# ReadyUNO_DIP.net
KiCad netlist of a schematic drawn in EAGLE
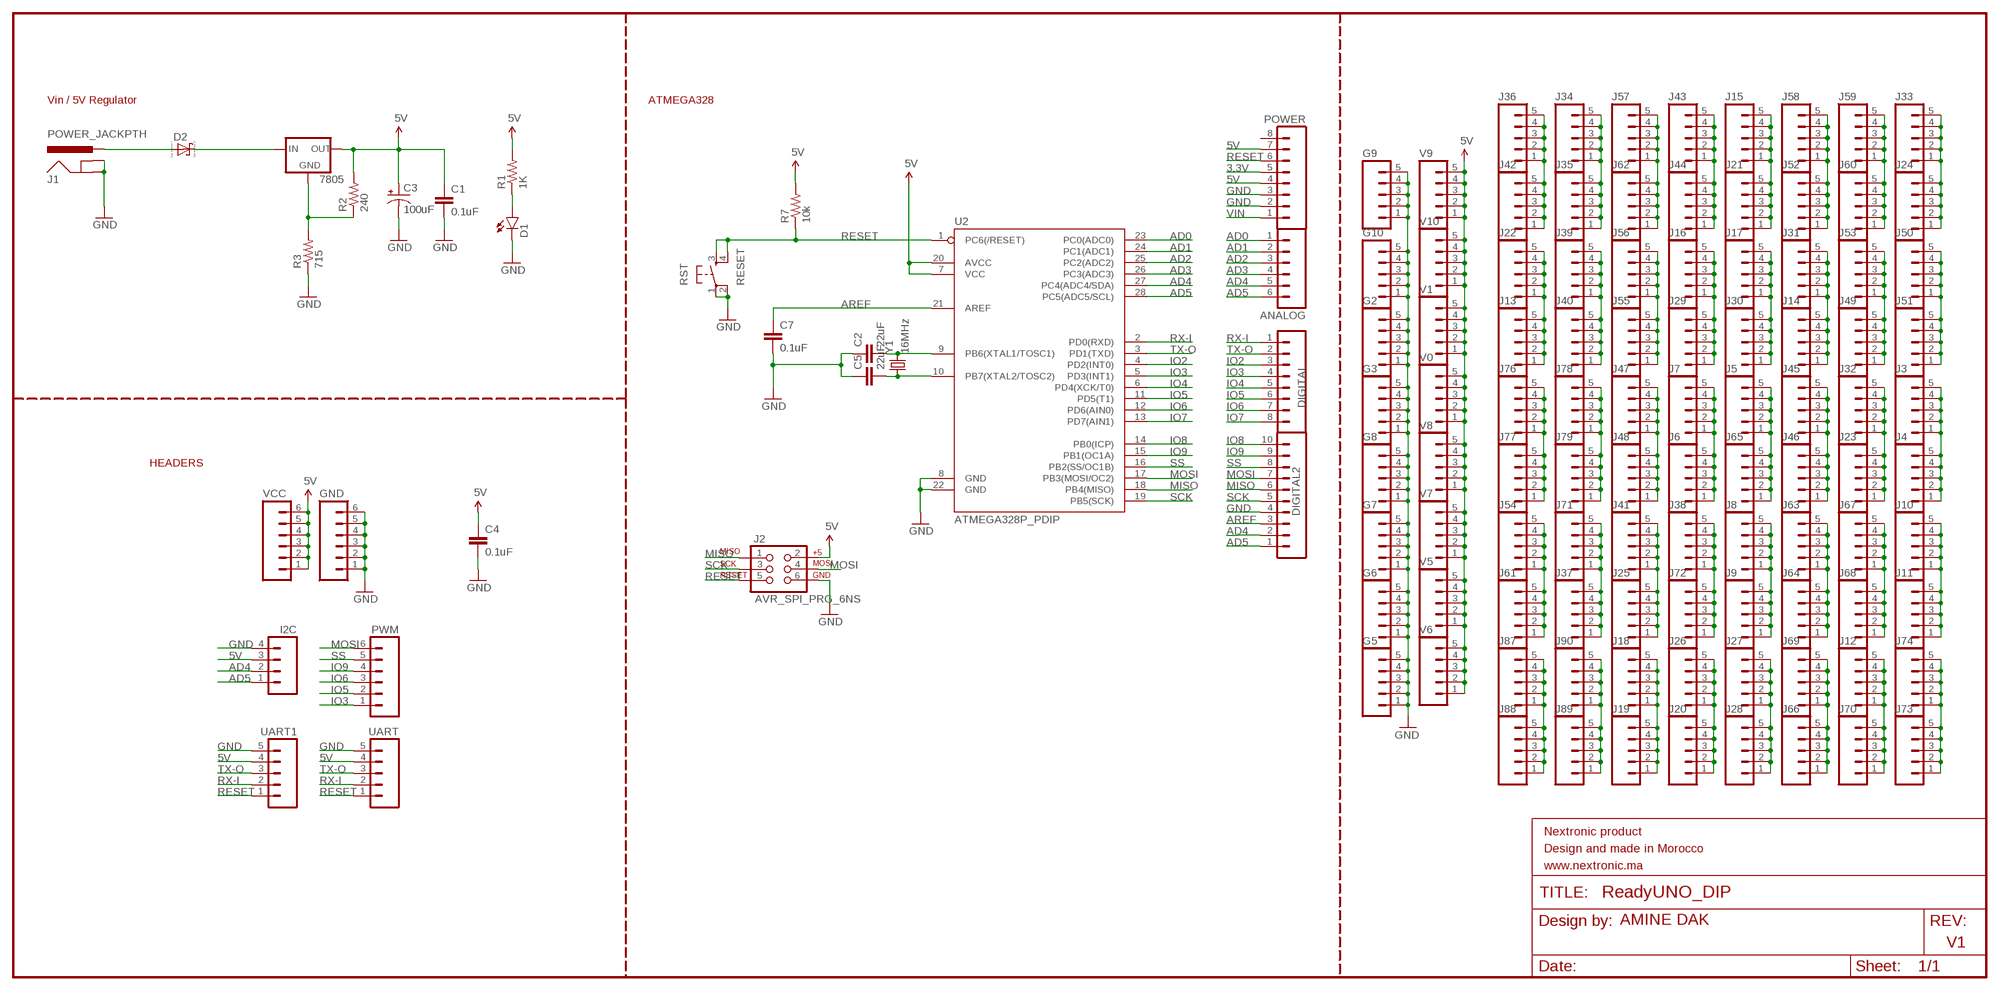
[diagram p0: schematic, sheet 1]

(export (version "E")
  (design (tool "Eeschema 10.0.6"))
  (components
    (comp (ref "7805")
      (value "V_REG_78XX-TO-220")
      (footprint "eagle-import:TO-220-ALT")
      (libsource (lib "eagle-import") (part "V_REG_78XX-TO-220"))
    )
    (comp (ref "ANALOG")
      (value "M06SILK_FEMALE_PTH")
      (footprint "eagle-import:1X06")
      (libsource (lib "eagle-import") (part "M06SILK_FEMALE_PTH"))
    )
    (comp (ref "C1")
      (value "0.1uF")
      (footprint "eagle-import:CAP-PTH-SMALLEZ")
      (fields (field (name "MF") "MULTICOMP") (field (name "MPN") "MCRR25104X7RK0050"))
      (libsource (lib "eagle-import") (part "CAPEZ"))
    )
    (comp (ref "C2")
      (value "22uF")
      (footprint "eagle-import:CAP-PTH-SMALLEZ")
      (fields (field (name "MF") "MULTICOMP") (field (name "MPN") "MCGPR100V226M8X11"))
      (libsource (lib "eagle-import") (part "CAPEZ"))
    )
    (comp (ref "C3")
      (value "100uF")
      (footprint "eagle-import:CPOL-RADIAL-100UF-25V")
      (fields (field (name "MF") "MULTICOMP") (field (name "MPN") "MCGPR25V107M6.3X11"))
      (libsource (lib "eagle-import") (part "CAP_POLPTH1"))
    )
    (comp (ref "C4")
      (value "0.1uF")
      (footprint "eagle-import:CAP-PTH-SMALLEZ")
      (fields (field (name "MF") "MULTICOMP") (field (name "MPN") "MCRR25104X7RK0050"))
      (libsource (lib "eagle-import") (part "CAPEZ"))
    )
    (comp (ref "C5")
      (value "22uF")
      (footprint "eagle-import:CAP-PTH-SMALLEZ")
      (fields (field (name "MF") "MULTICOMP") (field (name "MPN") "MCGPR100V226M8X11"))
      (libsource (lib "eagle-import") (part "CAPEZ"))
    )
    (comp (ref "C7")
      (value "0.1uF")
      (footprint "eagle-import:CAP-PTH-SMALLEZ")
      (fields (field (name "MF") "MULTICOMP") (field (name "MPN") "MCRR25104X7RK0050"))
      (libsource (lib "eagle-import") (part "CAPEZ"))
    )
    (comp (ref "D1")
      (value "LED-3MM-NO_SILK")
      (footprint "eagle-import:LED3MM-NS")
      (libsource (lib "eagle-import") (part "LED-3MM-NO_SILK"))
    )
    (comp (ref "D2")
      (value "SCHOTTKY-DIODEDO35-7")
      (footprint "eagle-import:DIODE_DO35-7")
      (libsource (lib "eagle-import") (part "SCHOTTKY-DIODEDO35-7"))
    )
    (comp (ref "DIGITAL")
      (value "M08SILK_FEMALE_PTH")
      (footprint "eagle-import:1X08")
      (libsource (lib "eagle-import") (part "M08SILK_FEMALE_PTH"))
    )
    (comp (ref "DIGITAL2")
      (value "M10SILK_FEMALE_PTH")
      (footprint "eagle-import:1X10")
      (libsource (lib "eagle-import") (part "M10SILK_FEMALE_PTH"))
    )
    (comp (ref "FRAME1")
      (value "FRAME-LETTER")
      (footprint "eagle-import:CREATIVE_COMMONS")
      (libsource (lib "eagle-import") (part "FRAME-LETTER"))
    )
    (comp (ref "G2")
      (value "M05PTH")
      (footprint "eagle-import:1X05")
      (libsource (lib "eagle-import") (part "M05PTH"))
    )
    (comp (ref "G3")
      (value "M05PTH")
      (footprint "eagle-import:1X05")
      (libsource (lib "eagle-import") (part "M05PTH"))
    )
    (comp (ref "G5")
      (value "M05PTH")
      (footprint "eagle-import:1X05")
      (libsource (lib "eagle-import") (part "M05PTH"))
    )
    (comp (ref "G6")
      (value "M05PTH")
      (footprint "eagle-import:1X05")
      (libsource (lib "eagle-import") (part "M05PTH"))
    )
    (comp (ref "G7")
      (value "M05PTH")
      (footprint "eagle-import:1X05")
      (libsource (lib "eagle-import") (part "M05PTH"))
    )
    (comp (ref "G8")
      (value "M05PTH")
      (footprint "eagle-import:1X05")
      (libsource (lib "eagle-import") (part "M05PTH"))
    )
    (comp (ref "G9")
      (value "M05PTH")
      (footprint "eagle-import:1X05")
      (libsource (lib "eagle-import") (part "M05PTH"))
    )
    (comp (ref "G10")
      (value "M05PTH")
      (footprint "eagle-import:1X05")
      (libsource (lib "eagle-import") (part "M05PTH"))
    )
    (comp (ref "GND")
      (value "M06SILK_FEMALE_PTH")
      (footprint "eagle-import:1X06")
      (libsource (lib "eagle-import") (part "M06SILK_FEMALE_PTH"))
    )
    (comp (ref "I2C")
      (value "M04PTH")
      (footprint "eagle-import:1X04")
      (libsource (lib "eagle-import") (part "M04PTH"))
    )
    (comp (ref "J1")
      (value "POWER_JACKPTH")
      (footprint "eagle-import:POWER_JACK_PTH")
      (libsource (lib "eagle-import") (part "POWER_JACKPTH"))
    )
    (comp (ref "J2")
      (value "AVR_SPI_PRG_6NS")
      (footprint "eagle-import:2X3-NS")
      (libsource (lib "eagle-import") (part "AVR_SPI_PRG_6NS"))
    )
    (comp (ref "J3")
      (value "M05PTH")
      (footprint "eagle-import:1X05")
      (libsource (lib "eagle-import") (part "M05PTH"))
    )
    (comp (ref "J4")
      (value "M05PTH")
      (footprint "eagle-import:1X05")
      (libsource (lib "eagle-import") (part "M05PTH"))
    )
    (comp (ref "J5")
      (value "M05PTH")
      (footprint "eagle-import:1X05")
      (libsource (lib "eagle-import") (part "M05PTH"))
    )
    (comp (ref "J6")
      (value "M05PTH")
      (footprint "eagle-import:1X05")
      (libsource (lib "eagle-import") (part "M05PTH"))
    )
    (comp (ref "J7")
      (value "M05PTH")
      (footprint "eagle-import:1X05")
      (libsource (lib "eagle-import") (part "M05PTH"))
    )
    (comp (ref "J8")
      (value "M05PTH")
      (footprint "eagle-import:1X05")
      (libsource (lib "eagle-import") (part "M05PTH"))
    )
    (comp (ref "J9")
      (value "M05PTH")
      (footprint "eagle-import:1X05")
      (libsource (lib "eagle-import") (part "M05PTH"))
    )
    (comp (ref "J10")
      (value "M05PTH")
      (footprint "eagle-import:1X05")
      (libsource (lib "eagle-import") (part "M05PTH"))
    )
    (comp (ref "J11")
      (value "M05PTH")
      (footprint "eagle-import:1X05")
      (libsource (lib "eagle-import") (part "M05PTH"))
    )
    (comp (ref "J12")
      (value "M05PTH")
      (footprint "eagle-import:1X05")
      (libsource (lib "eagle-import") (part "M05PTH"))
    )
    (comp (ref "J13")
      (value "M05PTH")
      (footprint "eagle-import:1X05")
      (libsource (lib "eagle-import") (part "M05PTH"))
    )
    (comp (ref "J14")
      (value "M05PTH")
      (footprint "eagle-import:1X05")
      (libsource (lib "eagle-import") (part "M05PTH"))
    )
    (comp (ref "J15")
      (value "M05PTH")
      (footprint "eagle-import:1X05")
      (libsource (lib "eagle-import") (part "M05PTH"))
    )
    (comp (ref "J16")
      (value "M05PTH")
      (footprint "eagle-import:1X05")
      (libsource (lib "eagle-import") (part "M05PTH"))
    )
    (comp (ref "J17")
      (value "M05PTH")
      (footprint "eagle-import:1X05")
      (libsource (lib "eagle-import") (part "M05PTH"))
    )
    (comp (ref "J18")
      (value "M05PTH")
      (footprint "eagle-import:1X05")
      (libsource (lib "eagle-import") (part "M05PTH"))
    )
    (comp (ref "J19")
      (value "M05PTH")
      (footprint "eagle-import:1X05")
      (libsource (lib "eagle-import") (part "M05PTH"))
    )
    (comp (ref "J20")
      (value "M05PTH")
      (footprint "eagle-import:1X05")
      (libsource (lib "eagle-import") (part "M05PTH"))
    )
    (comp (ref "J21")
      (value "M05PTH")
      (footprint "eagle-import:1X05")
      (libsource (lib "eagle-import") (part "M05PTH"))
    )
    (comp (ref "J22")
      (value "M05PTH")
      (footprint "eagle-import:1X05")
      (libsource (lib "eagle-import") (part "M05PTH"))
    )
    (comp (ref "J23")
      (value "M05PTH")
      (footprint "eagle-import:1X05")
      (libsource (lib "eagle-import") (part "M05PTH"))
    )
    (comp (ref "J24")
      (value "M05PTH")
      (footprint "eagle-import:1X05")
      (libsource (lib "eagle-import") (part "M05PTH"))
    )
    (comp (ref "J25")
      (value "M05PTH")
      (footprint "eagle-import:1X05")
      (libsource (lib "eagle-import") (part "M05PTH"))
    )
    (comp (ref "J26")
      (value "M05PTH")
      (footprint "eagle-import:1X05")
      (libsource (lib "eagle-import") (part "M05PTH"))
    )
    (comp (ref "J27")
      (value "M05PTH")
      (footprint "eagle-import:1X05")
      (libsource (lib "eagle-import") (part "M05PTH"))
    )
    (comp (ref "J28")
      (value "M05PTH")
      (footprint "eagle-import:1X05")
      (libsource (lib "eagle-import") (part "M05PTH"))
    )
    (comp (ref "J29")
      (value "M05PTH")
      (footprint "eagle-import:1X05")
      (libsource (lib "eagle-import") (part "M05PTH"))
    )
    (comp (ref "J30")
      (value "M05PTH")
      (footprint "eagle-import:1X05")
      (libsource (lib "eagle-import") (part "M05PTH"))
    )
    (comp (ref "J31")
      (value "M05PTH")
      (footprint "eagle-import:1X05")
      (libsource (lib "eagle-import") (part "M05PTH"))
    )
    (comp (ref "J32")
      (value "M05PTH")
      (footprint "eagle-import:1X05")
      (libsource (lib "eagle-import") (part "M05PTH"))
    )
    (comp (ref "J33")
      (value "M05PTH")
      (footprint "eagle-import:1X05")
      (libsource (lib "eagle-import") (part "M05PTH"))
    )
    (comp (ref "J34")
      (value "M05PTH")
      (footprint "eagle-import:1X05")
      (libsource (lib "eagle-import") (part "M05PTH"))
    )
    (comp (ref "J35")
      (value "M05PTH")
      (footprint "eagle-import:1X05")
      (libsource (lib "eagle-import") (part "M05PTH"))
    )
    (comp (ref "J36")
      (value "M05PTH")
      (footprint "eagle-import:1X05")
      (libsource (lib "eagle-import") (part "M05PTH"))
    )
    (comp (ref "J37")
      (value "M05PTH")
      (footprint "eagle-import:1X05")
      (libsource (lib "eagle-import") (part "M05PTH"))
    )
    (comp (ref "J38")
      (value "M05PTH")
      (footprint "eagle-import:1X05")
      (libsource (lib "eagle-import") (part "M05PTH"))
    )
    (comp (ref "J39")
      (value "M05PTH")
      (footprint "eagle-import:1X05")
      (libsource (lib "eagle-import") (part "M05PTH"))
    )
    (comp (ref "J40")
      (value "M05PTH")
      (footprint "eagle-import:1X05")
      (libsource (lib "eagle-import") (part "M05PTH"))
    )
    (comp (ref "J41")
      (value "M05PTH")
      (footprint "eagle-import:1X05")
      (libsource (lib "eagle-import") (part "M05PTH"))
    )
    (comp (ref "J42")
      (value "M05PTH")
      (footprint "eagle-import:1X05")
      (libsource (lib "eagle-import") (part "M05PTH"))
    )
    (comp (ref "J43")
      (value "M05PTH")
      (footprint "eagle-import:1X05")
      (libsource (lib "eagle-import") (part "M05PTH"))
    )
    (comp (ref "J44")
      (value "M05PTH")
      (footprint "eagle-import:1X05")
      (libsource (lib "eagle-import") (part "M05PTH"))
    )
    (comp (ref "J45")
      (value "M05PTH")
      (footprint "eagle-import:1X05")
      (libsource (lib "eagle-import") (part "M05PTH"))
    )
    (comp (ref "J46")
      (value "M05PTH")
      (footprint "eagle-import:1X05")
      (libsource (lib "eagle-import") (part "M05PTH"))
    )
    (comp (ref "J47")
      (value "M05PTH")
      (footprint "eagle-import:1X05")
      (libsource (lib "eagle-import") (part "M05PTH"))
    )
    (comp (ref "J48")
      (value "M05PTH")
      (footprint "eagle-import:1X05")
      (libsource (lib "eagle-import") (part "M05PTH"))
    )
    (comp (ref "J49")
      (value "M05PTH")
      (footprint "eagle-import:1X05")
      (libsource (lib "eagle-import") (part "M05PTH"))
    )
    (comp (ref "J50")
      (value "M05PTH")
      (footprint "eagle-import:1X05")
      (libsource (lib "eagle-import") (part "M05PTH"))
    )
    (comp (ref "J51")
      (value "M05PTH")
      (footprint "eagle-import:1X05")
      (libsource (lib "eagle-import") (part "M05PTH"))
    )
    (comp (ref "J52")
      (value "M05PTH")
      (footprint "eagle-import:1X05")
      (libsource (lib "eagle-import") (part "M05PTH"))
    )
    (comp (ref "J53")
      (value "M05PTH")
      (footprint "eagle-import:1X05")
      (libsource (lib "eagle-import") (part "M05PTH"))
    )
    (comp (ref "J54")
      (value "M05PTH")
      (footprint "eagle-import:1X05")
      (libsource (lib "eagle-import") (part "M05PTH"))
    )
    (comp (ref "J55")
      (value "M05PTH")
      (footprint "eagle-import:1X05")
      (libsource (lib "eagle-import") (part "M05PTH"))
    )
    (comp (ref "J56")
      (value "M05PTH")
      (footprint "eagle-import:1X05")
      (libsource (lib "eagle-import") (part "M05PTH"))
    )
    (comp (ref "J57")
      (value "M05PTH")
      (footprint "eagle-import:1X05")
      (libsource (lib "eagle-import") (part "M05PTH"))
    )
    (comp (ref "J58")
      (value "M05PTH")
      (footprint "eagle-import:1X05")
      (libsource (lib "eagle-import") (part "M05PTH"))
    )
    (comp (ref "J59")
      (value "M05PTH")
      (footprint "eagle-import:1X05")
      (libsource (lib "eagle-import") (part "M05PTH"))
    )
    (comp (ref "J60")
      (value "M05PTH")
      (footprint "eagle-import:1X05")
      (libsource (lib "eagle-import") (part "M05PTH"))
    )
    (comp (ref "J61")
      (value "M05PTH")
      (footprint "eagle-import:1X05")
      (libsource (lib "eagle-import") (part "M05PTH"))
    )
    (comp (ref "J62")
      (value "M05PTH")
      (footprint "eagle-import:1X05")
      (libsource (lib "eagle-import") (part "M05PTH"))
    )
    (comp (ref "J63")
      (value "M05PTH")
      (footprint "eagle-import:1X05")
      (libsource (lib "eagle-import") (part "M05PTH"))
    )
    (comp (ref "J64")
      (value "M05PTH")
      (footprint "eagle-import:1X05")
      (libsource (lib "eagle-import") (part "M05PTH"))
    )
    (comp (ref "J65")
      (value "M05PTH")
      (footprint "eagle-import:1X05")
      (libsource (lib "eagle-import") (part "M05PTH"))
    )
    (comp (ref "J66")
      (value "M05PTH")
      (footprint "eagle-import:1X05")
      (libsource (lib "eagle-import") (part "M05PTH"))
    )
    (comp (ref "J67")
      (value "M05PTH")
      (footprint "eagle-import:1X05")
      (libsource (lib "eagle-import") (part "M05PTH"))
    )
    (comp (ref "J68")
      (value "M05PTH")
      (footprint "eagle-import:1X05")
      (libsource (lib "eagle-import") (part "M05PTH"))
    )
    (comp (ref "J69")
      (value "M05PTH")
      (footprint "eagle-import:1X05")
      (libsource (lib "eagle-import") (part "M05PTH"))
    )
    (comp (ref "J70")
      (value "M05PTH")
      (footprint "eagle-import:1X05")
      (libsource (lib "eagle-import") (part "M05PTH"))
    )
    (comp (ref "J71")
      (value "M05PTH")
      (footprint "eagle-import:1X05")
      (libsource (lib "eagle-import") (part "M05PTH"))
    )
    (comp (ref "J72")
      (value "M05PTH")
      (footprint "eagle-import:1X05")
      (libsource (lib "eagle-import") (part "M05PTH"))
    )
    (comp (ref "J73")
      (value "M05PTH")
      (footprint "eagle-import:1X05")
      (libsource (lib "eagle-import") (part "M05PTH"))
    )
    (comp (ref "J74")
      (value "M05PTH")
      (footprint "eagle-import:1X05")
      (libsource (lib "eagle-import") (part "M05PTH"))
    )
    (comp (ref "J76")
      (value "M05PTH")
      (footprint "eagle-import:1X05")
      (libsource (lib "eagle-import") (part "M05PTH"))
    )
    (comp (ref "J77")
      (value "M05PTH")
      (footprint "eagle-import:1X05")
      (libsource (lib "eagle-import") (part "M05PTH"))
    )
    (comp (ref "J78")
      (value "M05PTH")
      (footprint "eagle-import:1X05")
      (libsource (lib "eagle-import") (part "M05PTH"))
    )
    (comp (ref "J79")
      (value "M05PTH")
      (footprint "eagle-import:1X05")
      (libsource (lib "eagle-import") (part "M05PTH"))
    )
    (comp (ref "J87")
      (value "M05PTH")
      (footprint "eagle-import:1X05")
      (libsource (lib "eagle-import") (part "M05PTH"))
    )
    (comp (ref "J88")
      (value "M05PTH")
      (footprint "eagle-import:1X05")
      (libsource (lib "eagle-import") (part "M05PTH"))
    )
    (comp (ref "J89")
      (value "M05PTH")
      (footprint "eagle-import:1X05")
      (libsource (lib "eagle-import") (part "M05PTH"))
    )
    (comp (ref "J90")
      (value "M05PTH")
      (footprint "eagle-import:1X05")
      (libsource (lib "eagle-import") (part "M05PTH"))
    )
    (comp (ref "POWER")
      (value "M08SILK_FEMALE_PTH")
      (footprint "eagle-import:1X08")
      (libsource (lib "eagle-import") (part "M08SILK_FEMALE_PTH"))
    )
    (comp (ref "PWM")
      (value "M06SILK_FEMALE_PTH")
      (footprint "eagle-import:1X06")
      (libsource (lib "eagle-import") (part "M06SILK_FEMALE_PTH"))
    )
    (comp (ref "R1")
      (value "1K")
      (footprint "eagle-import:AXIAL-0.3")
      (fields (field (name "MF") "MULTICOMP") (field (name "MPN") "MCRE000037"))
      (libsource (lib "eagle-import") (part "RESISTORAXIAL-0.3"))
    )
    (comp (ref "R2")
      (value "240")
      (footprint "eagle-import:AXIAL-0.3")
      (fields (field (name "MF") "WELWYN") (field (name "MPN") "MFR4-240RFI"))
      (libsource (lib "eagle-import") (part "RESISTORAXIAL-0.3"))
    )
    (comp (ref "R3")
      (value "715")
      (footprint "eagle-import:AXIAL-0.3")
      (fields (field (name "MF") "TE CONNECTIVITY / NEOHM") (field (name "MPN") "YR1B715RCC"))
      (libsource (lib "eagle-import") (part "RESISTORAXIAL-0.3"))
    )
    (comp (ref "R7")
      (value "10k")
      (footprint "eagle-import:AXIAL-0.3")
      (libsource (lib "eagle-import") (part "RESISTORAXIAL-0.3"))
    )
    (comp (ref "RST")
      (value "RESET")
      (footprint "eagle-import:TACTILE-PTH")
      (libsource (lib "eagle-import") (part "TAC_SWITCHPTH"))
    )
    (comp (ref "U2")
      (value "ATMEGA328P_PDIP")
      (footprint "eagle-import:DIL28-3")
      (fields (field (name "MF") "ATMEL") (field (name "MPN") "ATMEGA328-PU"))
      (libsource (lib "eagle-import") (part "ATMEGA328P_PDIP"))
    )
    (comp (ref "UART")
      (value "M05PTH")
      (footprint "eagle-import:1X05")
      (libsource (lib "eagle-import") (part "M05PTH"))
    )
    (comp (ref "UART1")
      (value "M05PTH")
      (footprint "eagle-import:1X05")
      (libsource (lib "eagle-import") (part "M05PTH"))
    )
    (comp (ref "V0")
      (value "M05PTH")
      (footprint "eagle-import:1X05")
      (libsource (lib "eagle-import") (part "M05PTH"))
    )
    (comp (ref "V1")
      (value "M05PTH")
      (footprint "eagle-import:1X05")
      (libsource (lib "eagle-import") (part "M05PTH"))
    )
    (comp (ref "V5")
      (value "M05PTH")
      (footprint "eagle-import:1X05")
      (libsource (lib "eagle-import") (part "M05PTH"))
    )
    (comp (ref "V6")
      (value "M05PTH")
      (footprint "eagle-import:1X05")
      (libsource (lib "eagle-import") (part "M05PTH"))
    )
    (comp (ref "V7")
      (value "M05PTH")
      (footprint "eagle-import:1X05")
      (libsource (lib "eagle-import") (part "M05PTH"))
    )
    (comp (ref "V8")
      (value "M05PTH")
      (footprint "eagle-import:1X05")
      (libsource (lib "eagle-import") (part "M05PTH"))
    )
    (comp (ref "V9")
      (value "M05PTH")
      (footprint "eagle-import:1X05")
      (libsource (lib "eagle-import") (part "M05PTH"))
    )
    (comp (ref "V10")
      (value "M05PTH")
      (footprint "eagle-import:1X05")
      (libsource (lib "eagle-import") (part "M05PTH"))
    )
    (comp (ref "VCC")
      (value "M06SILK_FEMALE_PTH")
      (footprint "eagle-import:1X06")
      (libsource (lib "eagle-import") (part "M06SILK_FEMALE_PTH"))
    )
    (comp (ref "Y1")
      (value "16MHz")
      (footprint "eagle-import:HC49US")
      (fields (field (name "MF") "RALTRON") (field (name "MPN") "AS-16.000-18"))
      (libsource (lib "eagle-import") (part "CRYSTALHC49US"))
    )
  )
  (nets
    (net (code "1") (name "/3.3V") (class "Default")
      (node (ref "POWER") (pin "5") (pinfunction "5_5") (pintype "passive"))
    )
    (net (code "2") (name "/AD0") (class "Default")
      (node (ref "ANALOG") (pin "1") (pinfunction "1_1") (pintype "passive"))
      (node (ref "U2") (pin "23") (pinfunction "PC0(ADC0)_23") (pintype "bidirectional"))
    )
    (net (code "3") (name "/AD1") (class "Default")
      (node (ref "ANALOG") (pin "2") (pinfunction "2_2") (pintype "passive"))
      (node (ref "U2") (pin "24") (pinfunction "PC1(ADC1)_24") (pintype "bidirectional"))
    )
    (net (code "4") (name "/AD2") (class "Default")
      (node (ref "ANALOG") (pin "3") (pinfunction "3_3") (pintype "passive"))
      (node (ref "U2") (pin "25") (pinfunction "PC2(ADC2)_25") (pintype "bidirectional"))
    )
    (net (code "5") (name "/AD3") (class "Default")
      (node (ref "ANALOG") (pin "4") (pinfunction "4_4") (pintype "passive"))
      (node (ref "U2") (pin "26") (pinfunction "PC3(ADC3)_26") (pintype "bidirectional"))
    )
    (net (code "6") (name "/AD4") (class "Default")
      (node (ref "ANALOG") (pin "5") (pinfunction "5_5") (pintype "passive"))
      (node (ref "DIGITAL2") (pin "2") (pinfunction "2_2") (pintype "passive"))
      (node (ref "I2C") (pin "2") (pinfunction "2_2") (pintype "passive"))
      (node (ref "U2") (pin "27") (pinfunction "PC4(ADC4/SDA)_27") (pintype "bidirectional"))
    )
    (net (code "7") (name "/AD5") (class "Default")
      (node (ref "ANALOG") (pin "6") (pinfunction "6_6") (pintype "passive"))
      (node (ref "DIGITAL2") (pin "1") (pinfunction "1_1") (pintype "passive"))
      (node (ref "I2C") (pin "1") (pinfunction "1_1") (pintype "passive"))
      (node (ref "U2") (pin "28") (pinfunction "PC5(ADC5/SCL)_28") (pintype "bidirectional"))
    )
    (net (code "8") (name "/AREF") (class "Default")
      (node (ref "C7") (pin "1") (pinfunction "1_1") (pintype "passive"))
      (node (ref "DIGITAL2") (pin "3") (pinfunction "3_3") (pintype "passive"))
      (node (ref "U2") (pin "21") (pinfunction "AREF_21") (pintype "bidirectional"))
    )
    (net (code "9") (name "/IO2") (class "Default")
      (node (ref "DIGITAL") (pin "3") (pinfunction "3_3") (pintype "passive"))
      (node (ref "U2") (pin "4") (pinfunction "PD2(INT0)_4") (pintype "bidirectional"))
    )
    (net (code "10") (name "/IO3") (class "Default")
      (node (ref "DIGITAL") (pin "4") (pinfunction "4_4") (pintype "passive"))
      (node (ref "PWM") (pin "1") (pinfunction "1_1") (pintype "passive"))
      (node (ref "U2") (pin "5") (pinfunction "PD3(INT1)_5") (pintype "bidirectional"))
    )
    (net (code "11") (name "/IO4") (class "Default")
      (node (ref "DIGITAL") (pin "5") (pinfunction "5_5") (pintype "passive"))
      (node (ref "U2") (pin "6") (pinfunction "PD4(XCK/T0)_6") (pintype "bidirectional"))
    )
    (net (code "12") (name "/IO5") (class "Default")
      (node (ref "DIGITAL") (pin "6") (pinfunction "6_6") (pintype "passive"))
      (node (ref "PWM") (pin "2") (pinfunction "2_2") (pintype "passive"))
      (node (ref "U2") (pin "11") (pinfunction "PD5(T1)_11") (pintype "bidirectional"))
    )
    (net (code "13") (name "/IO6") (class "Default")
      (node (ref "DIGITAL") (pin "7") (pinfunction "7_7") (pintype "passive"))
      (node (ref "PWM") (pin "3") (pinfunction "3_3") (pintype "passive"))
      (node (ref "U2") (pin "12") (pinfunction "PD6(AIN0)_12") (pintype "bidirectional"))
    )
    (net (code "14") (name "/IO7") (class "Default")
      (node (ref "DIGITAL") (pin "8") (pinfunction "8_8") (pintype "passive"))
      (node (ref "U2") (pin "13") (pinfunction "PD7(AIN1)_13") (pintype "bidirectional"))
    )
    (net (code "15") (name "/IO8") (class "Default")
      (node (ref "DIGITAL2") (pin "10") (pinfunction "10_10") (pintype "passive"))
      (node (ref "U2") (pin "14") (pinfunction "PB0(ICP)_14") (pintype "bidirectional"))
    )
    (net (code "16") (name "/IO9") (class "Default")
      (node (ref "DIGITAL2") (pin "9") (pinfunction "9_9") (pintype "passive"))
      (node (ref "PWM") (pin "4") (pinfunction "4_4") (pintype "passive"))
      (node (ref "U2") (pin "15") (pinfunction "PB1(OC1A)_15") (pintype "bidirectional"))
    )
    (net (code "17") (name "/MISO") (class "Default")
      (node (ref "DIGITAL2") (pin "6") (pinfunction "6_6") (pintype "passive"))
      (node (ref "J2") (pin "1") (pinfunction "1_1") (pintype "passive"))
      (node (ref "U2") (pin "18") (pinfunction "PB4(MISO)_18") (pintype "bidirectional"))
    )
    (net (code "18") (name "/MOSI") (class "Default")
      (node (ref "DIGITAL2") (pin "7") (pinfunction "7_7") (pintype "passive"))
      (node (ref "J2") (pin "4") (pinfunction "4_4") (pintype "passive"))
      (node (ref "PWM") (pin "6") (pinfunction "6_6") (pintype "passive"))
      (node (ref "U2") (pin "17") (pinfunction "PB3(MOSI/OC2)_17") (pintype "bidirectional"))
    )
    (net (code "19") (name "/RESET") (class "Default")
      (node (ref "J2") (pin "5") (pinfunction "5_5") (pintype "passive"))
      (node (ref "POWER") (pin "6") (pinfunction "6_6") (pintype "passive"))
      (node (ref "R7") (pin "P$1") (pinfunction "1_P$1") (pintype "passive"))
      (node (ref "RST") (pin "3") (pinfunction "3_3") (pintype "passive"))
      (node (ref "RST") (pin "4") (pinfunction "4_4") (pintype "passive"))
      (node (ref "U2") (pin "1") (pinfunction "PC6(/RESET)_1") (pintype "bidirectional"))
      (node (ref "UART") (pin "1") (pinfunction "1_1") (pintype "passive"))
      (node (ref "UART1") (pin "1") (pinfunction "1_1") (pintype "passive"))
    )
    (net (code "20") (name "/RX-I") (class "Default")
      (node (ref "DIGITAL") (pin "1") (pinfunction "1_1") (pintype "passive"))
      (node (ref "U2") (pin "2") (pinfunction "PD0(RXD)_2") (pintype "bidirectional"))
      (node (ref "UART") (pin "2") (pinfunction "2_2") (pintype "passive"))
      (node (ref "UART1") (pin "2") (pinfunction "2_2") (pintype "passive"))
    )
    (net (code "21") (name "/SCK") (class "Default")
      (node (ref "DIGITAL2") (pin "5") (pinfunction "5_5") (pintype "passive"))
      (node (ref "J2") (pin "3") (pinfunction "3_3") (pintype "passive"))
      (node (ref "U2") (pin "19") (pinfunction "PB5(SCK)_19") (pintype "bidirectional"))
    )
    (net (code "22") (name "/SS") (class "Default")
      (node (ref "DIGITAL2") (pin "8") (pinfunction "8_8") (pintype "passive"))
      (node (ref "PWM") (pin "5") (pinfunction "5_5") (pintype "passive"))
      (node (ref "U2") (pin "16") (pinfunction "PB2(SS/OC1B)_16") (pintype "bidirectional"))
    )
    (net (code "23") (name "/TX-O") (class "Default")
      (node (ref "DIGITAL") (pin "2") (pinfunction "2_2") (pintype "passive"))
      (node (ref "U2") (pin "3") (pinfunction "PD1(TXD)_3") (pintype "bidirectional"))
      (node (ref "UART") (pin "3") (pinfunction "3_3") (pintype "passive"))
      (node (ref "UART1") (pin "3") (pinfunction "3_3") (pintype "passive"))
    )
    (net (code "24") (name "/VIN") (class "Default")
      (node (ref "POWER") (pin "1") (pinfunction "1_1") (pintype "passive"))
    )
    (net (code "25") (name "5V") (class "Default")
      (node (ref "7805") (pin "OUT") (pinfunction "OUT_OUT") (pintype "passive"))
      (node (ref "C1") (pin "1") (pinfunction "1_1") (pintype "passive"))
      (node (ref "C3") (pin "1") (pinfunction "+_1") (pintype "passive"))
      (node (ref "C4") (pin "1") (pinfunction "1_1") (pintype "passive"))
      (node (ref "I2C") (pin "3") (pinfunction "3_3") (pintype "passive"))
      (node (ref "J2") (pin "2") (pinfunction "2_2") (pintype "passive"))
      (node (ref "POWER") (pin "4") (pinfunction "4_4") (pintype "passive"))
      (node (ref "POWER") (pin "7") (pinfunction "7_7") (pintype "passive"))
      (node (ref "R1") (pin "P$2") (pinfunction "2_P$2") (pintype "passive"))
      (node (ref "R2") (pin "P$2") (pinfunction "2_P$2") (pintype "passive"))
      (node (ref "R7") (pin "P$2") (pinfunction "2_P$2") (pintype "passive"))
      (node (ref "U2") (pin "20") (pinfunction "AVCC_20") (pintype "bidirectional"))
      (node (ref "U2") (pin "7") (pinfunction "VCC_7") (pintype "bidirectional"))
      (node (ref "UART") (pin "4") (pinfunction "4_4") (pintype "passive"))
      (node (ref "UART1") (pin "4") (pinfunction "4_4") (pintype "passive"))
      (node (ref "V0") (pin "1") (pinfunction "1_1") (pintype "passive"))
      (node (ref "V0") (pin "2") (pinfunction "2_2") (pintype "passive"))
      (node (ref "V0") (pin "3") (pinfunction "3_3") (pintype "passive"))
      (node (ref "V0") (pin "4") (pinfunction "4_4") (pintype "passive"))
      (node (ref "V0") (pin "5") (pinfunction "5_5") (pintype "passive"))
      (node (ref "V1") (pin "1") (pinfunction "1_1") (pintype "passive"))
      (node (ref "V1") (pin "2") (pinfunction "2_2") (pintype "passive"))
      (node (ref "V1") (pin "3") (pinfunction "3_3") (pintype "passive"))
      (node (ref "V1") (pin "4") (pinfunction "4_4") (pintype "passive"))
      (node (ref "V1") (pin "5") (pinfunction "5_5") (pintype "passive"))
      (node (ref "V10") (pin "1") (pinfunction "1_1") (pintype "passive"))
      (node (ref "V10") (pin "2") (pinfunction "2_2") (pintype "passive"))
      (node (ref "V10") (pin "3") (pinfunction "3_3") (pintype "passive"))
      (node (ref "V10") (pin "4") (pinfunction "4_4") (pintype "passive"))
      (node (ref "V10") (pin "5") (pinfunction "5_5") (pintype "passive"))
      (node (ref "V5") (pin "1") (pinfunction "1_1") (pintype "passive"))
      (node (ref "V5") (pin "2") (pinfunction "2_2") (pintype "passive"))
      (node (ref "V5") (pin "3") (pinfunction "3_3") (pintype "passive"))
      (node (ref "V5") (pin "4") (pinfunction "4_4") (pintype "passive"))
      (node (ref "V5") (pin "5") (pinfunction "5_5") (pintype "passive"))
      (node (ref "V6") (pin "1") (pinfunction "1_1") (pintype "passive"))
      (node (ref "V6") (pin "2") (pinfunction "2_2") (pintype "passive"))
      (node (ref "V6") (pin "3") (pinfunction "3_3") (pintype "passive"))
      (node (ref "V6") (pin "4") (pinfunction "4_4") (pintype "passive"))
      (node (ref "V6") (pin "5") (pinfunction "5_5") (pintype "passive"))
      (node (ref "V7") (pin "1") (pinfunction "1_1") (pintype "passive"))
      (node (ref "V7") (pin "2") (pinfunction "2_2") (pintype "passive"))
      (node (ref "V7") (pin "3") (pinfunction "3_3") (pintype "passive"))
      (node (ref "V7") (pin "4") (pinfunction "4_4") (pintype "passive"))
      (node (ref "V7") (pin "5") (pinfunction "5_5") (pintype "passive"))
      (node (ref "V8") (pin "1") (pinfunction "1_1") (pintype "passive"))
      (node (ref "V8") (pin "2") (pinfunction "2_2") (pintype "passive"))
      (node (ref "V8") (pin "3") (pinfunction "3_3") (pintype "passive"))
      (node (ref "V8") (pin "4") (pinfunction "4_4") (pintype "passive"))
      (node (ref "V8") (pin "5") (pinfunction "5_5") (pintype "passive"))
      (node (ref "V9") (pin "1") (pinfunction "1_1") (pintype "passive"))
      (node (ref "V9") (pin "2") (pinfunction "2_2") (pintype "passive"))
      (node (ref "V9") (pin "3") (pinfunction "3_3") (pintype "passive"))
      (node (ref "V9") (pin "4") (pinfunction "4_4") (pintype "passive"))
      (node (ref "V9") (pin "5") (pinfunction "5_5") (pintype "passive"))
      (node (ref "VCC") (pin "1") (pinfunction "1_1") (pintype "passive"))
      (node (ref "VCC") (pin "2") (pinfunction "2_2") (pintype "passive"))
      (node (ref "VCC") (pin "3") (pinfunction "3_3") (pintype "passive"))
      (node (ref "VCC") (pin "4") (pinfunction "4_4") (pintype "passive"))
      (node (ref "VCC") (pin "5") (pinfunction "5_5") (pintype "passive"))
      (node (ref "VCC") (pin "6") (pinfunction "6_6") (pintype "passive"))
    )
    (net (code "26") (name "GND") (class "Default")
      (node (ref "C1") (pin "2") (pinfunction "2_2") (pintype "passive"))
      (node (ref "C2") (pin "1") (pinfunction "1_1") (pintype "passive"))
      (node (ref "C3") (pin "2") (pinfunction "-_2") (pintype "passive"))
      (node (ref "C4") (pin "2") (pinfunction "2_2") (pintype "passive"))
      (node (ref "C5") (pin "1") (pinfunction "1_1") (pintype "passive"))
      (node (ref "C7") (pin "2") (pinfunction "2_2") (pintype "passive"))
      (node (ref "D1") (pin "K") (pinfunction "C_K") (pintype "passive"))
      (node (ref "DIGITAL2") (pin "4") (pinfunction "4_4") (pintype "passive"))
      (node (ref "G10") (pin "1") (pinfunction "1_1") (pintype "passive"))
      (node (ref "G10") (pin "2") (pinfunction "2_2") (pintype "passive"))
      (node (ref "G10") (pin "3") (pinfunction "3_3") (pintype "passive"))
      (node (ref "G10") (pin "4") (pinfunction "4_4") (pintype "passive"))
      (node (ref "G10") (pin "5") (pinfunction "5_5") (pintype "passive"))
      (node (ref "G2") (pin "1") (pinfunction "1_1") (pintype "passive"))
      (node (ref "G2") (pin "2") (pinfunction "2_2") (pintype "passive"))
      (node (ref "G2") (pin "3") (pinfunction "3_3") (pintype "passive"))
      (node (ref "G2") (pin "4") (pinfunction "4_4") (pintype "passive"))
      (node (ref "G2") (pin "5") (pinfunction "5_5") (pintype "passive"))
      (node (ref "G3") (pin "1") (pinfunction "1_1") (pintype "passive"))
      (node (ref "G3") (pin "2") (pinfunction "2_2") (pintype "passive"))
      (node (ref "G3") (pin "3") (pinfunction "3_3") (pintype "passive"))
      (node (ref "G3") (pin "4") (pinfunction "4_4") (pintype "passive"))
      (node (ref "G3") (pin "5") (pinfunction "5_5") (pintype "passive"))
      (node (ref "G5") (pin "1") (pinfunction "1_1") (pintype "passive"))
      (node (ref "G5") (pin "2") (pinfunction "2_2") (pintype "passive"))
      (node (ref "G5") (pin "3") (pinfunction "3_3") (pintype "passive"))
      (node (ref "G5") (pin "4") (pinfunction "4_4") (pintype "passive"))
      (node (ref "G5") (pin "5") (pinfunction "5_5") (pintype "passive"))
      (node (ref "G6") (pin "1") (pinfunction "1_1") (pintype "passive"))
      (node (ref "G6") (pin "2") (pinfunction "2_2") (pintype "passive"))
      (node (ref "G6") (pin "3") (pinfunction "3_3") (pintype "passive"))
      (node (ref "G6") (pin "4") (pinfunction "4_4") (pintype "passive"))
      (node (ref "G6") (pin "5") (pinfunction "5_5") (pintype "passive"))
      (node (ref "G7") (pin "1") (pinfunction "1_1") (pintype "passive"))
      (node (ref "G7") (pin "2") (pinfunction "2_2") (pintype "passive"))
      (node (ref "G7") (pin "3") (pinfunction "3_3") (pintype "passive"))
      (node (ref "G7") (pin "4") (pinfunction "4_4") (pintype "passive"))
      (node (ref "G7") (pin "5") (pinfunction "5_5") (pintype "passive"))
      (node (ref "G8") (pin "1") (pinfunction "1_1") (pintype "passive"))
      (node (ref "G8") (pin "2") (pinfunction "2_2") (pintype "passive"))
      (node (ref "G8") (pin "3") (pinfunction "3_3") (pintype "passive"))
      (node (ref "G8") (pin "4") (pinfunction "4_4") (pintype "passive"))
      (node (ref "G8") (pin "5") (pinfunction "5_5") (pintype "passive"))
      (node (ref "G9") (pin "1") (pinfunction "1_1") (pintype "passive"))
      (node (ref "G9") (pin "2") (pinfunction "2_2") (pintype "passive"))
      (node (ref "G9") (pin "3") (pinfunction "3_3") (pintype "passive"))
      (node (ref "G9") (pin "4") (pinfunction "4_4") (pintype "passive"))
      (node (ref "G9") (pin "5") (pinfunction "5_5") (pintype "passive"))
      (node (ref "GND") (pin "1") (pinfunction "1_1") (pintype "passive"))
      (node (ref "GND") (pin "2") (pinfunction "2_2") (pintype "passive"))
      (node (ref "GND") (pin "3") (pinfunction "3_3") (pintype "passive"))
      (node (ref "GND") (pin "4") (pinfunction "4_4") (pintype "passive"))
      (node (ref "GND") (pin "5") (pinfunction "5_5") (pintype "passive"))
      (node (ref "GND") (pin "6") (pinfunction "6_6") (pintype "passive"))
      (node (ref "I2C") (pin "4") (pinfunction "4_4") (pintype "passive"))
      (node (ref "J1") (pin "GND") (pinfunction "GND_GND") (pintype "bidirectional"))
      (node (ref "J1") (pin "GNDBREAK") (pinfunction "GNDBREAK_GNDBREAK") (pintype "bidirectional"))
      (node (ref "J2") (pin "6") (pinfunction "6_6") (pintype "passive"))
      (node (ref "POWER") (pin "2") (pinfunction "2_2") (pintype "passive"))
      (node (ref "POWER") (pin "3") (pinfunction "3_3") (pintype "passive"))
      (node (ref "R3") (pin "P$1") (pinfunction "1_P$1") (pintype "passive"))
      (node (ref "RST") (pin "1") (pinfunction "1_1") (pintype "passive"))
      (node (ref "RST") (pin "2") (pinfunction "2_2") (pintype "passive"))
      (node (ref "U2") (pin "22") (pinfunction "GND_22") (pintype "bidirectional"))
      (node (ref "U2") (pin "8") (pinfunction "GND_8") (pintype "bidirectional"))
      (node (ref "UART") (pin "5") (pinfunction "5_5") (pintype "passive"))
      (node (ref "UART1") (pin "5") (pinfunction "5_5") (pintype "passive"))
    )
    (net (code "27") (name "Net-(D2-A)") (class "Default")
      (node (ref "7805") (pin "IN") (pinfunction "IN_IN") (pintype "input"))
      (node (ref "D2") (pin "C") (pinfunction "A_C") (pintype "passive"))
    )
    (net (code "28") (name "Net-(D2-C)") (class "Default")
      (node (ref "D2") (pin "A") (pinfunction "C_A") (pintype "passive"))
      (node (ref "J1") (pin "PWR") (pinfunction "PWR_PWR") (pintype "bidirectional"))
    )
    (net (code "29") (name "Net-(J3-Pad1)") (class "Default")
      (node (ref "J3") (pin "1") (pinfunction "1_1") (pintype "passive"))
      (node (ref "J3") (pin "2") (pinfunction "2_2") (pintype "passive"))
      (node (ref "J3") (pin "3") (pinfunction "3_3") (pintype "passive"))
      (node (ref "J3") (pin "4") (pinfunction "4_4") (pintype "passive"))
      (node (ref "J3") (pin "5") (pinfunction "5_5") (pintype "passive"))
      (node (ref "J4") (pin "1") (pinfunction "1_1") (pintype "passive"))
      (node (ref "J4") (pin "2") (pinfunction "2_2") (pintype "passive"))
      (node (ref "J4") (pin "3") (pinfunction "3_3") (pintype "passive"))
      (node (ref "J4") (pin "4") (pinfunction "4_4") (pintype "passive"))
      (node (ref "J4") (pin "5") (pinfunction "5_5") (pintype "passive"))
    )
    (net (code "30") (name "Net-(J5-Pad1)") (class "Default")
      (node (ref "J5") (pin "1") (pinfunction "1_1") (pintype "passive"))
      (node (ref "J5") (pin "2") (pinfunction "2_2") (pintype "passive"))
      (node (ref "J5") (pin "3") (pinfunction "3_3") (pintype "passive"))
      (node (ref "J5") (pin "4") (pinfunction "4_4") (pintype "passive"))
      (node (ref "J5") (pin "5") (pinfunction "5_5") (pintype "passive"))
      (node (ref "J65") (pin "1") (pinfunction "1_1") (pintype "passive"))
      (node (ref "J65") (pin "2") (pinfunction "2_2") (pintype "passive"))
      (node (ref "J65") (pin "3") (pinfunction "3_3") (pintype "passive"))
      (node (ref "J65") (pin "4") (pinfunction "4_4") (pintype "passive"))
      (node (ref "J65") (pin "5") (pinfunction "5_5") (pintype "passive"))
    )
    (net (code "31") (name "Net-(J6-Pad1)") (class "Default")
      (node (ref "J6") (pin "1") (pinfunction "1_1") (pintype "passive"))
      (node (ref "J6") (pin "2") (pinfunction "2_2") (pintype "passive"))
      (node (ref "J6") (pin "3") (pinfunction "3_3") (pintype "passive"))
      (node (ref "J6") (pin "4") (pinfunction "4_4") (pintype "passive"))
      (node (ref "J6") (pin "5") (pinfunction "5_5") (pintype "passive"))
      (node (ref "J7") (pin "1") (pinfunction "1_1") (pintype "passive"))
      (node (ref "J7") (pin "2") (pinfunction "2_2") (pintype "passive"))
      (node (ref "J7") (pin "3") (pinfunction "3_3") (pintype "passive"))
      (node (ref "J7") (pin "4") (pinfunction "4_4") (pintype "passive"))
      (node (ref "J7") (pin "5") (pinfunction "5_5") (pintype "passive"))
    )
    (net (code "32") (name "Net-(J8-Pad1)") (class "Default")
      (node (ref "J8") (pin "1") (pinfunction "1_1") (pintype "passive"))
      (node (ref "J8") (pin "2") (pinfunction "2_2") (pintype "passive"))
      (node (ref "J8") (pin "3") (pinfunction "3_3") (pintype "passive"))
      (node (ref "J8") (pin "4") (pinfunction "4_4") (pintype "passive"))
      (node (ref "J8") (pin "5") (pinfunction "5_5") (pintype "passive"))
      (node (ref "J9") (pin "1") (pinfunction "1_1") (pintype "passive"))
      (node (ref "J9") (pin "2") (pinfunction "2_2") (pintype "passive"))
      (node (ref "J9") (pin "3") (pinfunction "3_3") (pintype "passive"))
      (node (ref "J9") (pin "4") (pinfunction "4_4") (pintype "passive"))
      (node (ref "J9") (pin "5") (pinfunction "5_5") (pintype "passive"))
    )
    (net (code "33") (name "Net-(J10-Pad1)") (class "Default")
      (node (ref "J10") (pin "1") (pinfunction "1_1") (pintype "passive"))
      (node (ref "J10") (pin "2") (pinfunction "2_2") (pintype "passive"))
      (node (ref "J10") (pin "3") (pinfunction "3_3") (pintype "passive"))
      (node (ref "J10") (pin "4") (pinfunction "4_4") (pintype "passive"))
      (node (ref "J10") (pin "5") (pinfunction "5_5") (pintype "passive"))
      (node (ref "J11") (pin "1") (pinfunction "1_1") (pintype "passive"))
      (node (ref "J11") (pin "2") (pinfunction "2_2") (pintype "passive"))
      (node (ref "J11") (pin "3") (pinfunction "3_3") (pintype "passive"))
      (node (ref "J11") (pin "4") (pinfunction "4_4") (pintype "passive"))
      (node (ref "J11") (pin "5") (pinfunction "5_5") (pintype "passive"))
    )
    (net (code "34") (name "Net-(J12-Pad1)") (class "Default")
      (node (ref "J12") (pin "1") (pinfunction "1_1") (pintype "passive"))
      (node (ref "J12") (pin "2") (pinfunction "2_2") (pintype "passive"))
      (node (ref "J12") (pin "3") (pinfunction "3_3") (pintype "passive"))
      (node (ref "J12") (pin "4") (pinfunction "4_4") (pintype "passive"))
      (node (ref "J12") (pin "5") (pinfunction "5_5") (pintype "passive"))
      (node (ref "J70") (pin "1") (pinfunction "1_1") (pintype "passive"))
      (node (ref "J70") (pin "2") (pinfunction "2_2") (pintype "passive"))
      (node (ref "J70") (pin "3") (pinfunction "3_3") (pintype "passive"))
      (node (ref "J70") (pin "4") (pinfunction "4_4") (pintype "passive"))
      (node (ref "J70") (pin "5") (pinfunction "5_5") (pintype "passive"))
    )
    (net (code "35") (name "Net-(J13-Pad1)") (class "Default")
      (node (ref "J13") (pin "1") (pinfunction "1_1") (pintype "passive"))
      (node (ref "J13") (pin "2") (pinfunction "2_2") (pintype "passive"))
      (node (ref "J13") (pin "3") (pinfunction "3_3") (pintype "passive"))
      (node (ref "J13") (pin "4") (pinfunction "4_4") (pintype "passive"))
      (node (ref "J13") (pin "5") (pinfunction "5_5") (pintype "passive"))
      (node (ref "J22") (pin "1") (pinfunction "1_1") (pintype "passive"))
      (node (ref "J22") (pin "2") (pinfunction "2_2") (pintype "passive"))
      (node (ref "J22") (pin "3") (pinfunction "3_3") (pintype "passive"))
      (node (ref "J22") (pin "4") (pinfunction "4_4") (pintype "passive"))
      (node (ref "J22") (pin "5") (pinfunction "5_5") (pintype "passive"))
    )
    (net (code "36") (name "Net-(J14-Pad1)") (class "Default")
      (node (ref "J14") (pin "1") (pinfunction "1_1") (pintype "passive"))
      (node (ref "J14") (pin "2") (pinfunction "2_2") (pintype "passive"))
      (node (ref "J14") (pin "3") (pinfunction "3_3") (pintype "passive"))
      (node (ref "J14") (pin "4") (pinfunction "4_4") (pintype "passive"))
      (node (ref "J14") (pin "5") (pinfunction "5_5") (pintype "passive"))
      (node (ref "J31") (pin "1") (pinfunction "1_1") (pintype "passive"))
      (node (ref "J31") (pin "2") (pinfunction "2_2") (pintype "passive"))
      (node (ref "J31") (pin "3") (pinfunction "3_3") (pintype "passive"))
      (node (ref "J31") (pin "4") (pinfunction "4_4") (pintype "passive"))
      (node (ref "J31") (pin "5") (pinfunction "5_5") (pintype "passive"))
    )
    (net (code "37") (name "Net-(J15-Pad1)") (class "Default")
      (node (ref "J15") (pin "1") (pinfunction "1_1") (pintype "passive"))
      (node (ref "J15") (pin "2") (pinfunction "2_2") (pintype "passive"))
      (node (ref "J15") (pin "3") (pinfunction "3_3") (pintype "passive"))
      (node (ref "J15") (pin "4") (pinfunction "4_4") (pintype "passive"))
      (node (ref "J15") (pin "5") (pinfunction "5_5") (pintype "passive"))
      (node (ref "J21") (pin "1") (pinfunction "1_1") (pintype "passive"))
      (node (ref "J21") (pin "2") (pinfunction "2_2") (pintype "passive"))
      (node (ref "J21") (pin "3") (pinfunction "3_3") (pintype "passive"))
      (node (ref "J21") (pin "4") (pinfunction "4_4") (pintype "passive"))
      (node (ref "J21") (pin "5") (pinfunction "5_5") (pintype "passive"))
    )
    (net (code "38") (name "Net-(J16-Pad1)") (class "Default")
      (node (ref "J16") (pin "1") (pinfunction "1_1") (pintype "passive"))
      (node (ref "J16") (pin "2") (pinfunction "2_2") (pintype "passive"))
      (node (ref "J16") (pin "3") (pinfunction "3_3") (pintype "passive"))
      (node (ref "J16") (pin "4") (pinfunction "4_4") (pintype "passive"))
      (node (ref "J16") (pin "5") (pinfunction "5_5") (pintype "passive"))
      (node (ref "J29") (pin "1") (pinfunction "1_1") (pintype "passive"))
      (node (ref "J29") (pin "2") (pinfunction "2_2") (pintype "passive"))
      (node (ref "J29") (pin "3") (pinfunction "3_3") (pintype "passive"))
      (node (ref "J29") (pin "4") (pinfunction "4_4") (pintype "passive"))
      (node (ref "J29") (pin "5") (pinfunction "5_5") (pintype "passive"))
    )
    (net (code "39") (name "Net-(J17-Pad1)") (class "Default")
      (node (ref "J17") (pin "1") (pinfunction "1_1") (pintype "passive"))
      (node (ref "J17") (pin "2") (pinfunction "2_2") (pintype "passive"))
      (node (ref "J17") (pin "3") (pinfunction "3_3") (pintype "passive"))
      (node (ref "J17") (pin "4") (pinfunction "4_4") (pintype "passive"))
      (node (ref "J17") (pin "5") (pinfunction "5_5") (pintype "passive"))
      (node (ref "J30") (pin "1") (pinfunction "1_1") (pintype "passive"))
      (node (ref "J30") (pin "2") (pinfunction "2_2") (pintype "passive"))
      (node (ref "J30") (pin "3") (pinfunction "3_3") (pintype "passive"))
      (node (ref "J30") (pin "4") (pinfunction "4_4") (pintype "passive"))
      (node (ref "J30") (pin "5") (pinfunction "5_5") (pintype "passive"))
    )
    (net (code "40") (name "Net-(J18-Pad1)") (class "Default")
      (node (ref "J18") (pin "1") (pinfunction "1_1") (pintype "passive"))
      (node (ref "J18") (pin "2") (pinfunction "2_2") (pintype "passive"))
      (node (ref "J18") (pin "3") (pinfunction "3_3") (pintype "passive"))
      (node (ref "J18") (pin "4") (pinfunction "4_4") (pintype "passive"))
      (node (ref "J18") (pin "5") (pinfunction "5_5") (pintype "passive"))
      (node (ref "J19") (pin "1") (pinfunction "1_1") (pintype "passive"))
      (node (ref "J19") (pin "2") (pinfunction "2_2") (pintype "passive"))
      (node (ref "J19") (pin "3") (pinfunction "3_3") (pintype "passive"))
      (node (ref "J19") (pin "4") (pinfunction "4_4") (pintype "passive"))
      (node (ref "J19") (pin "5") (pinfunction "5_5") (pintype "passive"))
    )
    (net (code "41") (name "Net-(J20-Pad1)") (class "Default")
      (node (ref "J20") (pin "1") (pinfunction "1_1") (pintype "passive"))
      (node (ref "J20") (pin "2") (pinfunction "2_2") (pintype "passive"))
      (node (ref "J20") (pin "3") (pinfunction "3_3") (pintype "passive"))
      (node (ref "J20") (pin "4") (pinfunction "4_4") (pintype "passive"))
      (node (ref "J20") (pin "5") (pinfunction "5_5") (pintype "passive"))
      (node (ref "J26") (pin "1") (pinfunction "1_1") (pintype "passive"))
      (node (ref "J26") (pin "2") (pinfunction "2_2") (pintype "passive"))
      (node (ref "J26") (pin "3") (pinfunction "3_3") (pintype "passive"))
      (node (ref "J26") (pin "4") (pinfunction "4_4") (pintype "passive"))
      (node (ref "J26") (pin "5") (pinfunction "5_5") (pintype "passive"))
    )
    (net (code "42") (name "Net-(J23-Pad1)") (class "Default")
      (node (ref "J23") (pin "1") (pinfunction "1_1") (pintype "passive"))
      (node (ref "J23") (pin "2") (pinfunction "2_2") (pintype "passive"))
      (node (ref "J23") (pin "3") (pinfunction "3_3") (pintype "passive"))
      (node (ref "J23") (pin "4") (pinfunction "4_4") (pintype "passive"))
      (node (ref "J23") (pin "5") (pinfunction "5_5") (pintype "passive"))
      (node (ref "J32") (pin "1") (pinfunction "1_1") (pintype "passive"))
      (node (ref "J32") (pin "2") (pinfunction "2_2") (pintype "passive"))
      (node (ref "J32") (pin "3") (pinfunction "3_3") (pintype "passive"))
      (node (ref "J32") (pin "4") (pinfunction "4_4") (pintype "passive"))
      (node (ref "J32") (pin "5") (pinfunction "5_5") (pintype "passive"))
    )
    (net (code "43") (name "Net-(J24-Pad1)") (class "Default")
      (node (ref "J24") (pin "1") (pinfunction "1_1") (pintype "passive"))
      (node (ref "J24") (pin "2") (pinfunction "2_2") (pintype "passive"))
      (node (ref "J24") (pin "3") (pinfunction "3_3") (pintype "passive"))
      (node (ref "J24") (pin "4") (pinfunction "4_4") (pintype "passive"))
      (node (ref "J24") (pin "5") (pinfunction "5_5") (pintype "passive"))
      (node (ref "J33") (pin "1") (pinfunction "1_1") (pintype "passive"))
      (node (ref "J33") (pin "2") (pinfunction "2_2") (pintype "passive"))
      (node (ref "J33") (pin "3") (pinfunction "3_3") (pintype "passive"))
      (node (ref "J33") (pin "4") (pinfunction "4_4") (pintype "passive"))
      (node (ref "J33") (pin "5") (pinfunction "5_5") (pintype "passive"))
    )
    (net (code "44") (name "Net-(J25-Pad1)") (class "Default")
      (node (ref "J25") (pin "1") (pinfunction "1_1") (pintype "passive"))
      (node (ref "J25") (pin "2") (pinfunction "2_2") (pintype "passive"))
      (node (ref "J25") (pin "3") (pinfunction "3_3") (pintype "passive"))
      (node (ref "J25") (pin "4") (pinfunction "4_4") (pintype "passive"))
      (node (ref "J25") (pin "5") (pinfunction "5_5") (pintype "passive"))
      (node (ref "J41") (pin "1") (pinfunction "1_1") (pintype "passive"))
      (node (ref "J41") (pin "2") (pinfunction "2_2") (pintype "passive"))
      (node (ref "J41") (pin "3") (pinfunction "3_3") (pintype "passive"))
      (node (ref "J41") (pin "4") (pinfunction "4_4") (pintype "passive"))
      (node (ref "J41") (pin "5") (pinfunction "5_5") (pintype "passive"))
    )
    (net (code "45") (name "Net-(J27-Pad1)") (class "Default")
      (node (ref "J27") (pin "1") (pinfunction "1_1") (pintype "passive"))
      (node (ref "J27") (pin "2") (pinfunction "2_2") (pintype "passive"))
      (node (ref "J27") (pin "3") (pinfunction "3_3") (pintype "passive"))
      (node (ref "J27") (pin "4") (pinfunction "4_4") (pintype "passive"))
      (node (ref "J27") (pin "5") (pinfunction "5_5") (pintype "passive"))
      (node (ref "J28") (pin "1") (pinfunction "1_1") (pintype "passive"))
      (node (ref "J28") (pin "2") (pinfunction "2_2") (pintype "passive"))
      (node (ref "J28") (pin "3") (pinfunction "3_3") (pintype "passive"))
      (node (ref "J28") (pin "4") (pinfunction "4_4") (pintype "passive"))
      (node (ref "J28") (pin "5") (pinfunction "5_5") (pintype "passive"))
    )
    (net (code "46") (name "Net-(J34-Pad1)") (class "Default")
      (node (ref "J34") (pin "1") (pinfunction "1_1") (pintype "passive"))
      (node (ref "J34") (pin "2") (pinfunction "2_2") (pintype "passive"))
      (node (ref "J34") (pin "3") (pinfunction "3_3") (pintype "passive"))
      (node (ref "J34") (pin "4") (pinfunction "4_4") (pintype "passive"))
      (node (ref "J34") (pin "5") (pinfunction "5_5") (pintype "passive"))
      (node (ref "J35") (pin "1") (pinfunction "1_1") (pintype "passive"))
      (node (ref "J35") (pin "2") (pinfunction "2_2") (pintype "passive"))
      (node (ref "J35") (pin "3") (pinfunction "3_3") (pintype "passive"))
      (node (ref "J35") (pin "4") (pinfunction "4_4") (pintype "passive"))
      (node (ref "J35") (pin "5") (pinfunction "5_5") (pintype "passive"))
    )
    (net (code "47") (name "Net-(J36-Pad1)") (class "Default")
      (node (ref "J36") (pin "1") (pinfunction "1_1") (pintype "passive"))
      (node (ref "J36") (pin "2") (pinfunction "2_2") (pintype "passive"))
      (node (ref "J36") (pin "3") (pinfunction "3_3") (pintype "passive"))
      (node (ref "J36") (pin "4") (pinfunction "4_4") (pintype "passive"))
      (node (ref "J36") (pin "5") (pinfunction "5_5") (pintype "passive"))
      (node (ref "J42") (pin "1") (pinfunction "1_1") (pintype "passive"))
      (node (ref "J42") (pin "2") (pinfunction "2_2") (pintype "passive"))
      (node (ref "J42") (pin "3") (pinfunction "3_3") (pintype "passive"))
      (node (ref "J42") (pin "4") (pinfunction "4_4") (pintype "passive"))
      (node (ref "J42") (pin "5") (pinfunction "5_5") (pintype "passive"))
    )
    (net (code "48") (name "Net-(J37-Pad1)") (class "Default")
      (node (ref "J37") (pin "1") (pinfunction "1_1") (pintype "passive"))
      (node (ref "J37") (pin "2") (pinfunction "2_2") (pintype "passive"))
      (node (ref "J37") (pin "3") (pinfunction "3_3") (pintype "passive"))
      (node (ref "J37") (pin "4") (pinfunction "4_4") (pintype "passive"))
      (node (ref "J37") (pin "5") (pinfunction "5_5") (pintype "passive"))
      (node (ref "J71") (pin "1") (pinfunction "1_1") (pintype "passive"))
      (node (ref "J71") (pin "2") (pinfunction "2_2") (pintype "passive"))
      (node (ref "J71") (pin "3") (pinfunction "3_3") (pintype "passive"))
      (node (ref "J71") (pin "4") (pinfunction "4_4") (pintype "passive"))
      (node (ref "J71") (pin "5") (pinfunction "5_5") (pintype "passive"))
    )
    (net (code "49") (name "Net-(J38-Pad1)") (class "Default")
      (node (ref "J38") (pin "1") (pinfunction "1_1") (pintype "passive"))
      (node (ref "J38") (pin "2") (pinfunction "2_2") (pintype "passive"))
      (node (ref "J38") (pin "3") (pinfunction "3_3") (pintype "passive"))
      (node (ref "J38") (pin "4") (pinfunction "4_4") (pintype "passive"))
      (node (ref "J38") (pin "5") (pinfunction "5_5") (pintype "passive"))
      (node (ref "J72") (pin "1") (pinfunction "1_1") (pintype "passive"))
      (node (ref "J72") (pin "2") (pinfunction "2_2") (pintype "passive"))
      (node (ref "J72") (pin "3") (pinfunction "3_3") (pintype "passive"))
      (node (ref "J72") (pin "4") (pinfunction "4_4") (pintype "passive"))
      (node (ref "J72") (pin "5") (pinfunction "5_5") (pintype "passive"))
    )
    (net (code "50") (name "Net-(J39-Pad1)") (class "Default")
      (node (ref "J39") (pin "1") (pinfunction "1_1") (pintype "passive"))
      (node (ref "J39") (pin "2") (pinfunction "2_2") (pintype "passive"))
      (node (ref "J39") (pin "3") (pinfunction "3_3") (pintype "passive"))
      (node (ref "J39") (pin "4") (pinfunction "4_4") (pintype "passive"))
      (node (ref "J39") (pin "5") (pinfunction "5_5") (pintype "passive"))
      (node (ref "J40") (pin "1") (pinfunction "1_1") (pintype "passive"))
      (node (ref "J40") (pin "2") (pinfunction "2_2") (pintype "passive"))
      (node (ref "J40") (pin "3") (pinfunction "3_3") (pintype "passive"))
      (node (ref "J40") (pin "4") (pinfunction "4_4") (pintype "passive"))
      (node (ref "J40") (pin "5") (pinfunction "5_5") (pintype "passive"))
    )
    (net (code "51") (name "Net-(J43-Pad1)") (class "Default")
      (node (ref "J43") (pin "1") (pinfunction "1_1") (pintype "passive"))
      (node (ref "J43") (pin "2") (pinfunction "2_2") (pintype "passive"))
      (node (ref "J43") (pin "3") (pinfunction "3_3") (pintype "passive"))
      (node (ref "J43") (pin "4") (pinfunction "4_4") (pintype "passive"))
      (node (ref "J43") (pin "5") (pinfunction "5_5") (pintype "passive"))
      (node (ref "J44") (pin "1") (pinfunction "1_1") (pintype "passive"))
      (node (ref "J44") (pin "2") (pinfunction "2_2") (pintype "passive"))
      (node (ref "J44") (pin "3") (pinfunction "3_3") (pintype "passive"))
      (node (ref "J44") (pin "4") (pinfunction "4_4") (pintype "passive"))
      (node (ref "J44") (pin "5") (pinfunction "5_5") (pintype "passive"))
    )
    (net (code "52") (name "Net-(J45-Pad1)") (class "Default")
      (node (ref "J45") (pin "1") (pinfunction "1_1") (pintype "passive"))
      (node (ref "J45") (pin "2") (pinfunction "2_2") (pintype "passive"))
      (node (ref "J45") (pin "3") (pinfunction "3_3") (pintype "passive"))
      (node (ref "J45") (pin "4") (pinfunction "4_4") (pintype "passive"))
      (node (ref "J45") (pin "5") (pinfunction "5_5") (pintype "passive"))
      (node (ref "J46") (pin "1") (pinfunction "1_1") (pintype "passive"))
      (node (ref "J46") (pin "2") (pinfunction "2_2") (pintype "passive"))
      (node (ref "J46") (pin "3") (pinfunction "3_3") (pintype "passive"))
      (node (ref "J46") (pin "4") (pinfunction "4_4") (pintype "passive"))
      (node (ref "J46") (pin "5") (pinfunction "5_5") (pintype "passive"))
    )
    (net (code "53") (name "Net-(J47-Pad1)") (class "Default")
      (node (ref "J47") (pin "1") (pinfunction "1_1") (pintype "passive"))
      (node (ref "J47") (pin "2") (pinfunction "2_2") (pintype "passive"))
      (node (ref "J47") (pin "3") (pinfunction "3_3") (pintype "passive"))
      (node (ref "J47") (pin "4") (pinfunction "4_4") (pintype "passive"))
      (node (ref "J47") (pin "5") (pinfunction "5_5") (pintype "passive"))
      (node (ref "J48") (pin "1") (pinfunction "1_1") (pintype "passive"))
      (node (ref "J48") (pin "2") (pinfunction "2_2") (pintype "passive"))
      (node (ref "J48") (pin "3") (pinfunction "3_3") (pintype "passive"))
      (node (ref "J48") (pin "4") (pinfunction "4_4") (pintype "passive"))
      (node (ref "J48") (pin "5") (pinfunction "5_5") (pintype "passive"))
    )
    (net (code "54") (name "Net-(J49-Pad1)") (class "Default")
      (node (ref "J49") (pin "1") (pinfunction "1_1") (pintype "passive"))
      (node (ref "J49") (pin "2") (pinfunction "2_2") (pintype "passive"))
      (node (ref "J49") (pin "3") (pinfunction "3_3") (pintype "passive"))
      (node (ref "J49") (pin "4") (pinfunction "4_4") (pintype "passive"))
      (node (ref "J49") (pin "5") (pinfunction "5_5") (pintype "passive"))
      (node (ref "J53") (pin "1") (pinfunction "1_1") (pintype "passive"))
      (node (ref "J53") (pin "2") (pinfunction "2_2") (pintype "passive"))
      (node (ref "J53") (pin "3") (pinfunction "3_3") (pintype "passive"))
      (node (ref "J53") (pin "4") (pinfunction "4_4") (pintype "passive"))
      (node (ref "J53") (pin "5") (pinfunction "5_5") (pintype "passive"))
    )
    (net (code "55") (name "Net-(J50-Pad1)") (class "Default")
      (node (ref "J50") (pin "1") (pinfunction "1_1") (pintype "passive"))
      (node (ref "J50") (pin "2") (pinfunction "2_2") (pintype "passive"))
      (node (ref "J50") (pin "3") (pinfunction "3_3") (pintype "passive"))
      (node (ref "J50") (pin "4") (pinfunction "4_4") (pintype "passive"))
      (node (ref "J50") (pin "5") (pinfunction "5_5") (pintype "passive"))
      (node (ref "J51") (pin "1") (pinfunction "1_1") (pintype "passive"))
      (node (ref "J51") (pin "2") (pinfunction "2_2") (pintype "passive"))
      (node (ref "J51") (pin "3") (pinfunction "3_3") (pintype "passive"))
      (node (ref "J51") (pin "4") (pinfunction "4_4") (pintype "passive"))
      (node (ref "J51") (pin "5") (pinfunction "5_5") (pintype "passive"))
    )
    (net (code "56") (name "Net-(J52-Pad1)") (class "Default")
      (node (ref "J52") (pin "1") (pinfunction "1_1") (pintype "passive"))
      (node (ref "J52") (pin "2") (pinfunction "2_2") (pintype "passive"))
      (node (ref "J52") (pin "3") (pinfunction "3_3") (pintype "passive"))
      (node (ref "J52") (pin "4") (pinfunction "4_4") (pintype "passive"))
      (node (ref "J52") (pin "5") (pinfunction "5_5") (pintype "passive"))
      (node (ref "J58") (pin "1") (pinfunction "1_1") (pintype "passive"))
      (node (ref "J58") (pin "2") (pinfunction "2_2") (pintype "passive"))
      (node (ref "J58") (pin "3") (pinfunction "3_3") (pintype "passive"))
      (node (ref "J58") (pin "4") (pinfunction "4_4") (pintype "passive"))
      (node (ref "J58") (pin "5") (pinfunction "5_5") (pintype "passive"))
    )
    (net (code "57") (name "Net-(J54-Pad1)") (class "Default")
      (node (ref "J54") (pin "1") (pinfunction "1_1") (pintype "passive"))
      (node (ref "J54") (pin "2") (pinfunction "2_2") (pintype "passive"))
      (node (ref "J54") (pin "3") (pinfunction "3_3") (pintype "passive"))
      (node (ref "J54") (pin "4") (pinfunction "4_4") (pintype "passive"))
      (node (ref "J54") (pin "5") (pinfunction "5_5") (pintype "passive"))
      (node (ref "J61") (pin "1") (pinfunction "1_1") (pintype "passive"))
      (node (ref "J61") (pin "2") (pinfunction "2_2") (pintype "passive"))
      (node (ref "J61") (pin "3") (pinfunction "3_3") (pintype "passive"))
      (node (ref "J61") (pin "4") (pinfunction "4_4") (pintype "passive"))
      (node (ref "J61") (pin "5") (pinfunction "5_5") (pintype "passive"))
    )
    (net (code "58") (name "Net-(J55-Pad1)") (class "Default")
      (node (ref "J55") (pin "1") (pinfunction "1_1") (pintype "passive"))
      (node (ref "J55") (pin "2") (pinfunction "2_2") (pintype "passive"))
      (node (ref "J55") (pin "3") (pinfunction "3_3") (pintype "passive"))
      (node (ref "J55") (pin "4") (pinfunction "4_4") (pintype "passive"))
      (node (ref "J55") (pin "5") (pinfunction "5_5") (pintype "passive"))
      (node (ref "J56") (pin "1") (pinfunction "1_1") (pintype "passive"))
      (node (ref "J56") (pin "2") (pinfunction "2_2") (pintype "passive"))
      (node (ref "J56") (pin "3") (pinfunction "3_3") (pintype "passive"))
      (node (ref "J56") (pin "4") (pinfunction "4_4") (pintype "passive"))
      (node (ref "J56") (pin "5") (pinfunction "5_5") (pintype "passive"))
    )
    (net (code "59") (name "Net-(J57-Pad1)") (class "Default")
      (node (ref "J57") (pin "1") (pinfunction "1_1") (pintype "passive"))
      (node (ref "J57") (pin "2") (pinfunction "2_2") (pintype "passive"))
      (node (ref "J57") (pin "3") (pinfunction "3_3") (pintype "passive"))
      (node (ref "J57") (pin "4") (pinfunction "4_4") (pintype "passive"))
      (node (ref "J57") (pin "5") (pinfunction "5_5") (pintype "passive"))
      (node (ref "J62") (pin "1") (pinfunction "1_1") (pintype "passive"))
      (node (ref "J62") (pin "2") (pinfunction "2_2") (pintype "passive"))
      (node (ref "J62") (pin "3") (pinfunction "3_3") (pintype "passive"))
      (node (ref "J62") (pin "4") (pinfunction "4_4") (pintype "passive"))
      (node (ref "J62") (pin "5") (pinfunction "5_5") (pintype "passive"))
    )
    (net (code "60") (name "Net-(J59-Pad1)") (class "Default")
      (node (ref "J59") (pin "1") (pinfunction "1_1") (pintype "passive"))
      (node (ref "J59") (pin "2") (pinfunction "2_2") (pintype "passive"))
      (node (ref "J59") (pin "3") (pinfunction "3_3") (pintype "passive"))
      (node (ref "J59") (pin "4") (pinfunction "4_4") (pintype "passive"))
      (node (ref "J59") (pin "5") (pinfunction "5_5") (pintype "passive"))
      (node (ref "J60") (pin "1") (pinfunction "1_1") (pintype "passive"))
      (node (ref "J60") (pin "2") (pinfunction "2_2") (pintype "passive"))
      (node (ref "J60") (pin "3") (pinfunction "3_3") (pintype "passive"))
      (node (ref "J60") (pin "4") (pinfunction "4_4") (pintype "passive"))
      (node (ref "J60") (pin "5") (pinfunction "5_5") (pintype "passive"))
    )
    (net (code "61") (name "Net-(J63-Pad1)") (class "Default")
      (node (ref "J63") (pin "1") (pinfunction "1_1") (pintype "passive"))
      (node (ref "J63") (pin "2") (pinfunction "2_2") (pintype "passive"))
      (node (ref "J63") (pin "3") (pinfunction "3_3") (pintype "passive"))
      (node (ref "J63") (pin "4") (pinfunction "4_4") (pintype "passive"))
      (node (ref "J63") (pin "5") (pinfunction "5_5") (pintype "passive"))
      (node (ref "J64") (pin "1") (pinfunction "1_1") (pintype "passive"))
      (node (ref "J64") (pin "2") (pinfunction "2_2") (pintype "passive"))
      (node (ref "J64") (pin "3") (pinfunction "3_3") (pintype "passive"))
      (node (ref "J64") (pin "4") (pinfunction "4_4") (pintype "passive"))
      (node (ref "J64") (pin "5") (pinfunction "5_5") (pintype "passive"))
    )
    (net (code "62") (name "Net-(J66-Pad1)") (class "Default")
      (node (ref "J66") (pin "1") (pinfunction "1_1") (pintype "passive"))
      (node (ref "J66") (pin "2") (pinfunction "2_2") (pintype "passive"))
      (node (ref "J66") (pin "3") (pinfunction "3_3") (pintype "passive"))
      (node (ref "J66") (pin "4") (pinfunction "4_4") (pintype "passive"))
      (node (ref "J66") (pin "5") (pinfunction "5_5") (pintype "passive"))
      (node (ref "J69") (pin "1") (pinfunction "1_1") (pintype "passive"))
      (node (ref "J69") (pin "2") (pinfunction "2_2") (pintype "passive"))
      (node (ref "J69") (pin "3") (pinfunction "3_3") (pintype "passive"))
      (node (ref "J69") (pin "4") (pinfunction "4_4") (pintype "passive"))
      (node (ref "J69") (pin "5") (pinfunction "5_5") (pintype "passive"))
    )
    (net (code "63") (name "Net-(J67-Pad1)") (class "Default")
      (node (ref "J67") (pin "1") (pinfunction "1_1") (pintype "passive"))
      (node (ref "J67") (pin "2") (pinfunction "2_2") (pintype "passive"))
      (node (ref "J67") (pin "3") (pinfunction "3_3") (pintype "passive"))
      (node (ref "J67") (pin "4") (pinfunction "4_4") (pintype "passive"))
      (node (ref "J67") (pin "5") (pinfunction "5_5") (pintype "passive"))
      (node (ref "J68") (pin "1") (pinfunction "1_1") (pintype "passive"))
      (node (ref "J68") (pin "2") (pinfunction "2_2") (pintype "passive"))
      (node (ref "J68") (pin "3") (pinfunction "3_3") (pintype "passive"))
      (node (ref "J68") (pin "4") (pinfunction "4_4") (pintype "passive"))
      (node (ref "J68") (pin "5") (pinfunction "5_5") (pintype "passive"))
    )
    (net (code "64") (name "Net-(J73-Pad1)") (class "Default")
      (node (ref "J73") (pin "1") (pinfunction "1_1") (pintype "passive"))
      (node (ref "J73") (pin "2") (pinfunction "2_2") (pintype "passive"))
      (node (ref "J73") (pin "3") (pinfunction "3_3") (pintype "passive"))
      (node (ref "J73") (pin "4") (pinfunction "4_4") (pintype "passive"))
      (node (ref "J73") (pin "5") (pinfunction "5_5") (pintype "passive"))
      (node (ref "J74") (pin "1") (pinfunction "1_1") (pintype "passive"))
      (node (ref "J74") (pin "2") (pinfunction "2_2") (pintype "passive"))
      (node (ref "J74") (pin "3") (pinfunction "3_3") (pintype "passive"))
      (node (ref "J74") (pin "4") (pinfunction "4_4") (pintype "passive"))
      (node (ref "J74") (pin "5") (pinfunction "5_5") (pintype "passive"))
    )
    (net (code "65") (name "Net-(J76-Pad1)") (class "Default")
      (node (ref "J76") (pin "1") (pinfunction "1_1") (pintype "passive"))
      (node (ref "J76") (pin "2") (pinfunction "2_2") (pintype "passive"))
      (node (ref "J76") (pin "3") (pinfunction "3_3") (pintype "passive"))
      (node (ref "J76") (pin "4") (pinfunction "4_4") (pintype "passive"))
      (node (ref "J76") (pin "5") (pinfunction "5_5") (pintype "passive"))
      (node (ref "J77") (pin "1") (pinfunction "1_1") (pintype "passive"))
      (node (ref "J77") (pin "2") (pinfunction "2_2") (pintype "passive"))
      (node (ref "J77") (pin "3") (pinfunction "3_3") (pintype "passive"))
      (node (ref "J77") (pin "4") (pinfunction "4_4") (pintype "passive"))
      (node (ref "J77") (pin "5") (pinfunction "5_5") (pintype "passive"))
    )
    (net (code "66") (name "Net-(J78-Pad1)") (class "Default")
      (node (ref "J78") (pin "1") (pinfunction "1_1") (pintype "passive"))
      (node (ref "J78") (pin "2") (pinfunction "2_2") (pintype "passive"))
      (node (ref "J78") (pin "3") (pinfunction "3_3") (pintype "passive"))
      (node (ref "J78") (pin "4") (pinfunction "4_4") (pintype "passive"))
      (node (ref "J78") (pin "5") (pinfunction "5_5") (pintype "passive"))
      (node (ref "J79") (pin "1") (pinfunction "1_1") (pintype "passive"))
      (node (ref "J79") (pin "2") (pinfunction "2_2") (pintype "passive"))
      (node (ref "J79") (pin "3") (pinfunction "3_3") (pintype "passive"))
      (node (ref "J79") (pin "4") (pinfunction "4_4") (pintype "passive"))
      (node (ref "J79") (pin "5") (pinfunction "5_5") (pintype "passive"))
    )
    (net (code "67") (name "Net-(J87-Pad1)") (class "Default")
      (node (ref "J87") (pin "1") (pinfunction "1_1") (pintype "passive"))
      (node (ref "J87") (pin "2") (pinfunction "2_2") (pintype "passive"))
      (node (ref "J87") (pin "3") (pinfunction "3_3") (pintype "passive"))
      (node (ref "J87") (pin "4") (pinfunction "4_4") (pintype "passive"))
      (node (ref "J87") (pin "5") (pinfunction "5_5") (pintype "passive"))
      (node (ref "J88") (pin "1") (pinfunction "1_1") (pintype "passive"))
      (node (ref "J88") (pin "2") (pinfunction "2_2") (pintype "passive"))
      (node (ref "J88") (pin "3") (pinfunction "3_3") (pintype "passive"))
      (node (ref "J88") (pin "4") (pinfunction "4_4") (pintype "passive"))
      (node (ref "J88") (pin "5") (pinfunction "5_5") (pintype "passive"))
    )
    (net (code "68") (name "Net-(J89-Pad1)") (class "Default")
      (node (ref "J89") (pin "1") (pinfunction "1_1") (pintype "passive"))
      (node (ref "J89") (pin "2") (pinfunction "2_2") (pintype "passive"))
      (node (ref "J89") (pin "3") (pinfunction "3_3") (pintype "passive"))
      (node (ref "J89") (pin "4") (pinfunction "4_4") (pintype "passive"))
      (node (ref "J89") (pin "5") (pinfunction "5_5") (pintype "passive"))
      (node (ref "J90") (pin "1") (pinfunction "1_1") (pintype "passive"))
      (node (ref "J90") (pin "2") (pinfunction "2_2") (pintype "passive"))
      (node (ref "J90") (pin "3") (pinfunction "3_3") (pintype "passive"))
      (node (ref "J90") (pin "4") (pinfunction "4_4") (pintype "passive"))
      (node (ref "J90") (pin "5") (pinfunction "5_5") (pintype "passive"))
    )
    (net (code "69") (name "Net-(R1-1)") (class "Default")
      (node (ref "D1") (pin "A") (pinfunction "A_A") (pintype "passive"))
      (node (ref "R1") (pin "P$1") (pinfunction "1_P$1") (pintype "passive"))
    )
    (net (code "70") (name "Net-(R2-1)") (class "Default")
      (node (ref "7805") (pin "GND") (pinfunction "GND_GND") (pintype "input"))
      (node (ref "R2") (pin "P$1") (pinfunction "1_P$1") (pintype "passive"))
      (node (ref "R3") (pin "P$2") (pinfunction "2_P$2") (pintype "passive"))
    )
    (net (code "71") (name "Net-(U2-PB6(XTAL1{slash}TOSC1))") (class "Default")
      (node (ref "C2") (pin "2") (pinfunction "2_2") (pintype "passive"))
      (node (ref "U2") (pin "9") (pinfunction "PB6(XTAL1/TOSC1)_9") (pintype "bidirectional"))
      (node (ref "Y1") (pin "2") (pinfunction "2_2") (pintype "passive"))
    )
    (net (code "72") (name "Net-(U2-PB7(XTAL2{slash}TOSC2))") (class "Default")
      (node (ref "C5") (pin "2") (pinfunction "2_2") (pintype "passive"))
      (node (ref "U2") (pin "10") (pinfunction "PB7(XTAL2/TOSC2)_10") (pintype "bidirectional"))
      (node (ref "Y1") (pin "1") (pinfunction "1_1") (pintype "passive"))
    )
    (net (code "73") (name "unconnected-(POWER-Pad8)") (class "Default")
      (node (ref "POWER") (pin "8") (pinfunction "8_8") (pintype "passive"))
    )
  )
)
